# untitled.net
KiCad netlist of a schematic drawn in EAGLE
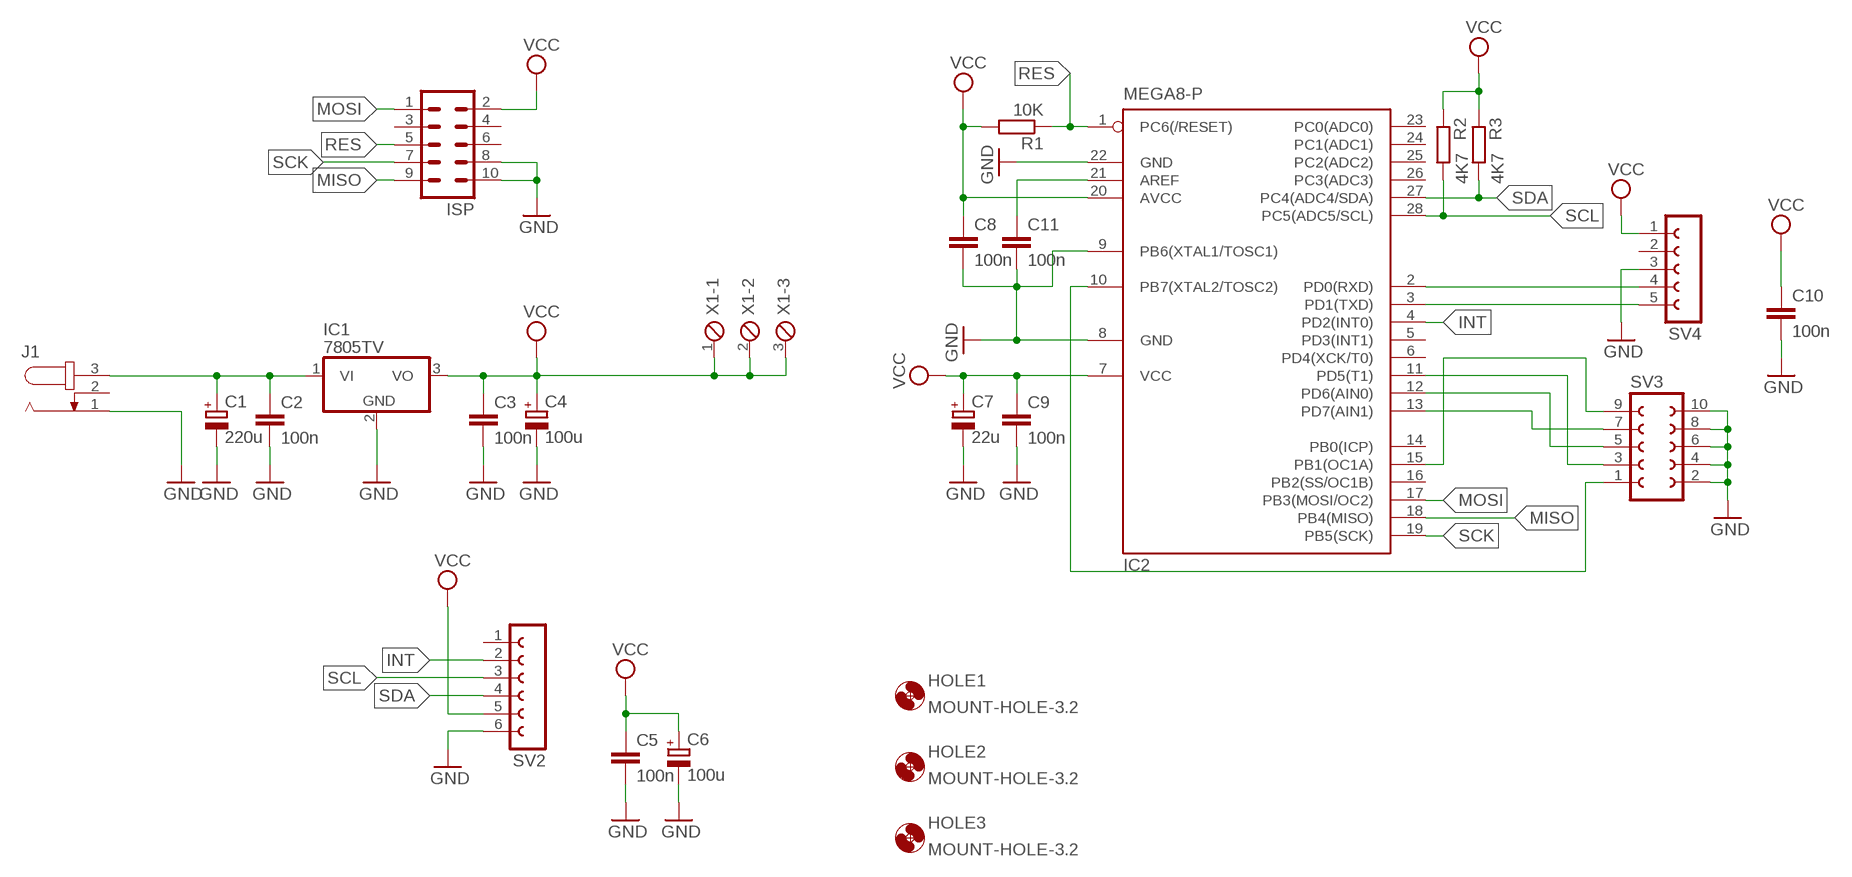
[diagram p0: schematic, sheet 1]

(export (version "E")
  (design (tool "Eeschema 10.0.6"))
  (components
    (comp (ref "C1")
      (value "220u")
      (footprint "eagle-import:E3,5-8")
      (libsource (lib "eagle-import") (part "CPOL-EUE3.5-8"))
    )
    (comp (ref "C2")
      (value "100n")
      (footprint "eagle-import:C0805")
      (libsource (lib "eagle-import") (part "C-EUC0805"))
    )
    (comp (ref "C3")
      (value "100n")
      (footprint "eagle-import:C0805")
      (libsource (lib "eagle-import") (part "C-EUC0805"))
    )
    (comp (ref "C4")
      (value "100u")
      (footprint "eagle-import:E2,5-5")
      (libsource (lib "eagle-import") (part "CPOL-EUE2.5-5"))
    )
    (comp (ref "C5")
      (value "100n")
      (footprint "eagle-import:C0805")
      (libsource (lib "eagle-import") (part "C-EUC0805"))
    )
    (comp (ref "C6")
      (value "100u")
      (footprint "eagle-import:E2,5-5")
      (libsource (lib "eagle-import") (part "CPOL-EUE2.5-5"))
    )
    (comp (ref "C7")
      (value "22u")
      (footprint "eagle-import:E2,5-5")
      (libsource (lib "eagle-import") (part "CPOL-EUE2.5-5"))
    )
    (comp (ref "C8")
      (value "100n")
      (footprint "eagle-import:C0805")
      (libsource (lib "eagle-import") (part "C-EUC0805"))
    )
    (comp (ref "C9")
      (value "100n")
      (footprint "eagle-import:C0805")
      (libsource (lib "eagle-import") (part "C-EUC0805"))
    )
    (comp (ref "C10")
      (value "100n")
      (footprint "eagle-import:C0805")
      (libsource (lib "eagle-import") (part "C-EUC0805"))
    )
    (comp (ref "C11")
      (value "100n")
      (footprint "eagle-import:C0805")
      (libsource (lib "eagle-import") (part "C-EUC0805"))
    )
    (comp (ref "HOLE1")
      (value "MOUNT-HOLE-3.2")
      (footprint "eagle-import:3,2")
      (libsource (lib "eagle-import") (part "MOUNT-HOLE-3.2"))
    )
    (comp (ref "HOLE2")
      (value "MOUNT-HOLE-3.2")
      (footprint "eagle-import:3,2")
      (libsource (lib "eagle-import") (part "MOUNT-HOLE-3.2"))
    )
    (comp (ref "HOLE3")
      (value "MOUNT-HOLE-3.2")
      (footprint "eagle-import:3,2")
      (libsource (lib "eagle-import") (part "MOUNT-HOLE-3.2"))
    )
    (comp (ref "IC1")
      (value "7805TV")
      (footprint "eagle-import:TO220V")
      (libsource (lib "eagle-import") (part "78TV05"))
    )
    (comp (ref "IC2")
      (value "MEGA8-P")
      (footprint "eagle-import:DIL28-3")
      (libsource (lib "eagle-import") (part "MEGA8-P"))
    )
    (comp (ref "ISP")
      (value "ML10")
      (footprint "eagle-import:ML10")
      (libsource (lib "eagle-import") (part "ML10"))
    )
    (comp (ref "J1")
      (value "JACK-PLUG1")
      (footprint "eagle-import:SPC4078")
      (libsource (lib "eagle-import") (part "JACK-PLUG1"))
    )
    (comp (ref "R1")
      (value "10K")
      (footprint "eagle-import:R0805")
      (libsource (lib "eagle-import") (part "R-EU_R0805"))
    )
    (comp (ref "R2")
      (value "4K7")
      (footprint "eagle-import:R0805")
      (libsource (lib "eagle-import") (part "R-EU_R0805"))
    )
    (comp (ref "R3")
      (value "4K7")
      (footprint "eagle-import:R0805")
      (libsource (lib "eagle-import") (part "R-EU_R0805"))
    )
    (comp (ref "SV2")
      (value "FE06-1")
      (footprint "eagle-import:FE06")
      (libsource (lib "eagle-import") (part "FE06-1"))
    )
    (comp (ref "SV3")
      (value "FE05-2")
      (footprint "eagle-import:FE05-2")
      (libsource (lib "eagle-import") (part "FE05-2"))
    )
    (comp (ref "SV4")
      (value "FE05-1")
      (footprint "eagle-import:FE05-1")
      (libsource (lib "eagle-import") (part "FE05-1"))
    )
    (comp (ref "X1")
      (value "MPT3")
      (footprint "eagle-import:3POL254")
      (libsource (lib "eagle-import") (part "MPT3"))
    )
  )
  (nets
    (net (code "1") (name "GND") (class "Default")
      (node (ref "C1") (pin "-") (pinfunction "-_-") (pintype "passive"))
      (node (ref "C10") (pin "2") (pinfunction "2_2") (pintype "passive"))
      (node (ref "C11") (pin "2") (pinfunction "2_2") (pintype "passive"))
      (node (ref "C2") (pin "2") (pinfunction "2_2") (pintype "passive"))
      (node (ref "C3") (pin "2") (pinfunction "2_2") (pintype "passive"))
      (node (ref "C4") (pin "-") (pinfunction "-_-") (pintype "passive"))
      (node (ref "C5") (pin "2") (pinfunction "2_2") (pintype "passive"))
      (node (ref "C6") (pin "-") (pinfunction "-_-") (pintype "passive"))
      (node (ref "C7") (pin "-") (pinfunction "-_-") (pintype "passive"))
      (node (ref "C8") (pin "2") (pinfunction "2_2") (pintype "passive"))
      (node (ref "C9") (pin "2") (pinfunction "2_2") (pintype "passive"))
      (node (ref "IC1") (pin "2") (pinfunction "GND_2") (pintype "passive"))
      (node (ref "IC2") (pin "22") (pinfunction "GND_22") (pintype "power_in"))
      (node (ref "IC2") (pin "8") (pinfunction "GND_8") (pintype "power_in"))
      (node (ref "IC2") (pin "9") (pinfunction "PB6(XTAL1/TOSC1)_9") (pintype "bidirectional"))
      (node (ref "ISP") (pin "10") (pinfunction "10_10") (pintype "passive"))
      (node (ref "ISP") (pin "8") (pinfunction "8_8") (pintype "passive"))
      (node (ref "J1") (pin "1") (pinfunction "1_1") (pintype "passive"))
      (node (ref "SV2") (pin "6") (pinfunction "6_6") (pintype "passive"))
      (node (ref "SV3") (pin "10") (pinfunction "10_10") (pintype "passive"))
      (node (ref "SV3") (pin "2") (pinfunction "2_2") (pintype "passive"))
      (node (ref "SV3") (pin "4") (pinfunction "4_4") (pintype "passive"))
      (node (ref "SV3") (pin "6") (pinfunction "6_6") (pintype "passive"))
      (node (ref "SV3") (pin "8") (pinfunction "8_8") (pintype "passive"))
      (node (ref "SV4") (pin "3") (pinfunction "3_3") (pintype "passive"))
    )
    (net (code "2") (name "INT") (class "Default")
      (node (ref "IC2") (pin "4") (pinfunction "PD2(INT0)_4") (pintype "bidirectional"))
      (node (ref "SV2") (pin "2") (pinfunction "2_2") (pintype "passive"))
    )
    (net (code "3") (name "MISO") (class "Default")
      (node (ref "IC2") (pin "18") (pinfunction "PB4(MISO)_18") (pintype "bidirectional"))
      (node (ref "ISP") (pin "9") (pinfunction "9_9") (pintype "passive"))
    )
    (net (code "4") (name "MOSI") (class "Default")
      (node (ref "IC2") (pin "17") (pinfunction "PB3(MOSI/OC2)_17") (pintype "bidirectional"))
      (node (ref "ISP") (pin "1") (pinfunction "1_1") (pintype "passive"))
    )
    (net (code "5") (name "Net-(IC1-VI)") (class "Default")
      (node (ref "C1") (pin "+") (pinfunction "+_+") (pintype "passive"))
      (node (ref "C2") (pin "1") (pinfunction "1_1") (pintype "passive"))
      (node (ref "IC1") (pin "1") (pinfunction "VI_1") (pintype "input"))
      (node (ref "J1") (pin "3") (pinfunction "3_3") (pintype "passive"))
    )
    (net (code "6") (name "Net-(IC2-AREF)") (class "Default")
      (node (ref "C11") (pin "1") (pinfunction "1_1") (pintype "passive"))
      (node (ref "IC2") (pin "21") (pinfunction "AREF_21") (pintype "passive"))
    )
    (net (code "7") (name "Net-(IC2-PB1(OC1A))") (class "Default")
      (node (ref "IC2") (pin "15") (pinfunction "PB1(OC1A)_15") (pintype "bidirectional"))
      (node (ref "SV3") (pin "9") (pinfunction "9_9") (pintype "passive"))
    )
    (net (code "8") (name "Net-(IC2-PB7(XTAL2{slash}TOSC2))") (class "Default")
      (node (ref "IC2") (pin "10") (pinfunction "PB7(XTAL2/TOSC2)_10") (pintype "bidirectional"))
      (node (ref "SV3") (pin "1") (pinfunction "1_1") (pintype "passive"))
    )
    (net (code "9") (name "Net-(IC2-PD0(RXD))") (class "Default")
      (node (ref "IC2") (pin "2") (pinfunction "PD0(RXD)_2") (pintype "bidirectional"))
      (node (ref "SV4") (pin "4") (pinfunction "4_4") (pintype "passive"))
    )
    (net (code "10") (name "Net-(IC2-PD1(TXD))") (class "Default")
      (node (ref "IC2") (pin "3") (pinfunction "PD1(TXD)_3") (pintype "bidirectional"))
      (node (ref "SV4") (pin "5") (pinfunction "5_5") (pintype "passive"))
    )
    (net (code "11") (name "Net-(IC2-PD5(T1))") (class "Default")
      (node (ref "IC2") (pin "11") (pinfunction "PD5(T1)_11") (pintype "bidirectional"))
      (node (ref "SV3") (pin "3") (pinfunction "3_3") (pintype "passive"))
    )
    (net (code "12") (name "Net-(IC2-PD6(AIN0))") (class "Default")
      (node (ref "IC2") (pin "12") (pinfunction "PD6(AIN0)_12") (pintype "bidirectional"))
      (node (ref "SV3") (pin "5") (pinfunction "5_5") (pintype "passive"))
    )
    (net (code "13") (name "Net-(IC2-PD7(AIN1))") (class "Default")
      (node (ref "IC2") (pin "13") (pinfunction "PD7(AIN1)_13") (pintype "bidirectional"))
      (node (ref "SV3") (pin "7") (pinfunction "7_7") (pintype "passive"))
    )
    (net (code "14") (name "RES") (class "Default")
      (node (ref "IC2") (pin "1") (pinfunction "PC6(/RESET)_1") (pintype "bidirectional"))
      (node (ref "ISP") (pin "5") (pinfunction "5_5") (pintype "passive"))
      (node (ref "R1") (pin "1") (pinfunction "1_1") (pintype "passive"))
    )
    (net (code "15") (name "SCK") (class "Default")
      (node (ref "IC2") (pin "19") (pinfunction "PB5(SCK)_19") (pintype "bidirectional"))
      (node (ref "ISP") (pin "7") (pinfunction "7_7") (pintype "passive"))
    )
    (net (code "16") (name "SCL") (class "Default")
      (node (ref "IC2") (pin "28") (pinfunction "PC5(ADC5/SCL)_28") (pintype "bidirectional"))
      (node (ref "R2") (pin "2") (pinfunction "2_2") (pintype "passive"))
      (node (ref "SV2") (pin "3") (pinfunction "3_3") (pintype "passive"))
    )
    (net (code "17") (name "SDA") (class "Default")
      (node (ref "IC2") (pin "27") (pinfunction "PC4(ADC4/SDA)_27") (pintype "bidirectional"))
      (node (ref "R3") (pin "2") (pinfunction "2_2") (pintype "passive"))
      (node (ref "SV2") (pin "4") (pinfunction "4_4") (pintype "passive"))
    )
    (net (code "18") (name "VCC") (class "Default")
      (node (ref "C10") (pin "1") (pinfunction "1_1") (pintype "passive"))
      (node (ref "C3") (pin "1") (pinfunction "1_1") (pintype "passive"))
      (node (ref "C4") (pin "+") (pinfunction "+_+") (pintype "passive"))
      (node (ref "C5") (pin "1") (pinfunction "1_1") (pintype "passive"))
      (node (ref "C6") (pin "+") (pinfunction "+_+") (pintype "passive"))
      (node (ref "C7") (pin "+") (pinfunction "+_+") (pintype "passive"))
      (node (ref "C8") (pin "1") (pinfunction "1_1") (pintype "passive"))
      (node (ref "C9") (pin "1") (pinfunction "1_1") (pintype "passive"))
      (node (ref "IC1") (pin "3") (pinfunction "VO_3") (pintype "passive"))
      (node (ref "IC2") (pin "20") (pinfunction "AVCC_20") (pintype "power_in"))
      (node (ref "IC2") (pin "7") (pinfunction "VCC_7") (pintype "power_in"))
      (node (ref "ISP") (pin "2") (pinfunction "2_2") (pintype "passive"))
      (node (ref "R1") (pin "2") (pinfunction "2_2") (pintype "passive"))
      (node (ref "R2") (pin "1") (pinfunction "1_1") (pintype "passive"))
      (node (ref "R3") (pin "1") (pinfunction "1_1") (pintype "passive"))
      (node (ref "SV2") (pin "5") (pinfunction "5_5") (pintype "passive"))
      (node (ref "SV4") (pin "1") (pinfunction "1_1") (pintype "passive"))
      (node (ref "X1") (pin "1") (pinfunction "1_1") (pintype "passive"))
      (node (ref "X1") (pin "2") (pinfunction "1_2") (pintype "passive"))
      (node (ref "X1") (pin "3") (pinfunction "1_3") (pintype "passive"))
    )
    (net (code "19") (name "unconnected-(IC2-PB0(ICP)-Pad14)") (class "Default")
      (node (ref "IC2") (pin "14") (pinfunction "PB0(ICP)_14") (pintype "bidirectional"))
    )
    (net (code "20") (name "unconnected-(IC2-PB2(SS{slash}OC1B)-Pad16)") (class "Default")
      (node (ref "IC2") (pin "16") (pinfunction "PB2(SS/OC1B)_16") (pintype "bidirectional"))
    )
    (net (code "21") (name "unconnected-(IC2-PC0(ADC0)-Pad23)") (class "Default")
      (node (ref "IC2") (pin "23") (pinfunction "PC0(ADC0)_23") (pintype "bidirectional"))
    )
    (net (code "22") (name "unconnected-(IC2-PC1(ADC1)-Pad24)") (class "Default")
      (node (ref "IC2") (pin "24") (pinfunction "PC1(ADC1)_24") (pintype "bidirectional"))
    )
    (net (code "23") (name "unconnected-(IC2-PC2(ADC2)-Pad25)") (class "Default")
      (node (ref "IC2") (pin "25") (pinfunction "PC2(ADC2)_25") (pintype "bidirectional"))
    )
    (net (code "24") (name "unconnected-(IC2-PC3(ADC3)-Pad26)") (class "Default")
      (node (ref "IC2") (pin "26") (pinfunction "PC3(ADC3)_26") (pintype "bidirectional"))
    )
    (net (code "25") (name "unconnected-(IC2-PD3(INT1)-Pad5)") (class "Default")
      (node (ref "IC2") (pin "5") (pinfunction "PD3(INT1)_5") (pintype "bidirectional"))
    )
    (net (code "26") (name "unconnected-(IC2-PD4(XCK{slash}T0)-Pad6)") (class "Default")
      (node (ref "IC2") (pin "6") (pinfunction "PD4(XCK/T0)_6") (pintype "bidirectional"))
    )
    (net (code "27") (name "unconnected-(ISP-Pad3)") (class "Default")
      (node (ref "ISP") (pin "3") (pinfunction "3_3") (pintype "passive"))
    )
    (net (code "28") (name "unconnected-(ISP-Pad4)") (class "Default")
      (node (ref "ISP") (pin "4") (pinfunction "4_4") (pintype "passive"))
    )
    (net (code "29") (name "unconnected-(ISP-Pad6)") (class "Default")
      (node (ref "ISP") (pin "6") (pinfunction "6_6") (pintype "passive"))
    )
    (net (code "30") (name "unconnected-(J1-Pad2)") (class "Default")
      (node (ref "J1") (pin "2") (pinfunction "2_2") (pintype "passive"))
    )
    (net (code "31") (name "unconnected-(SV2-Pad1)") (class "Default")
      (node (ref "SV2") (pin "1") (pinfunction "1_1") (pintype "passive"))
    )
    (net (code "32") (name "unconnected-(SV4-Pad2)") (class "Default")
      (node (ref "SV4") (pin "2") (pinfunction "2_2") (pintype "passive"))
    )
  )
)
